# Rover-6_Power_Supply.net
KiCad netlist of a schematic drawn in EAGLE
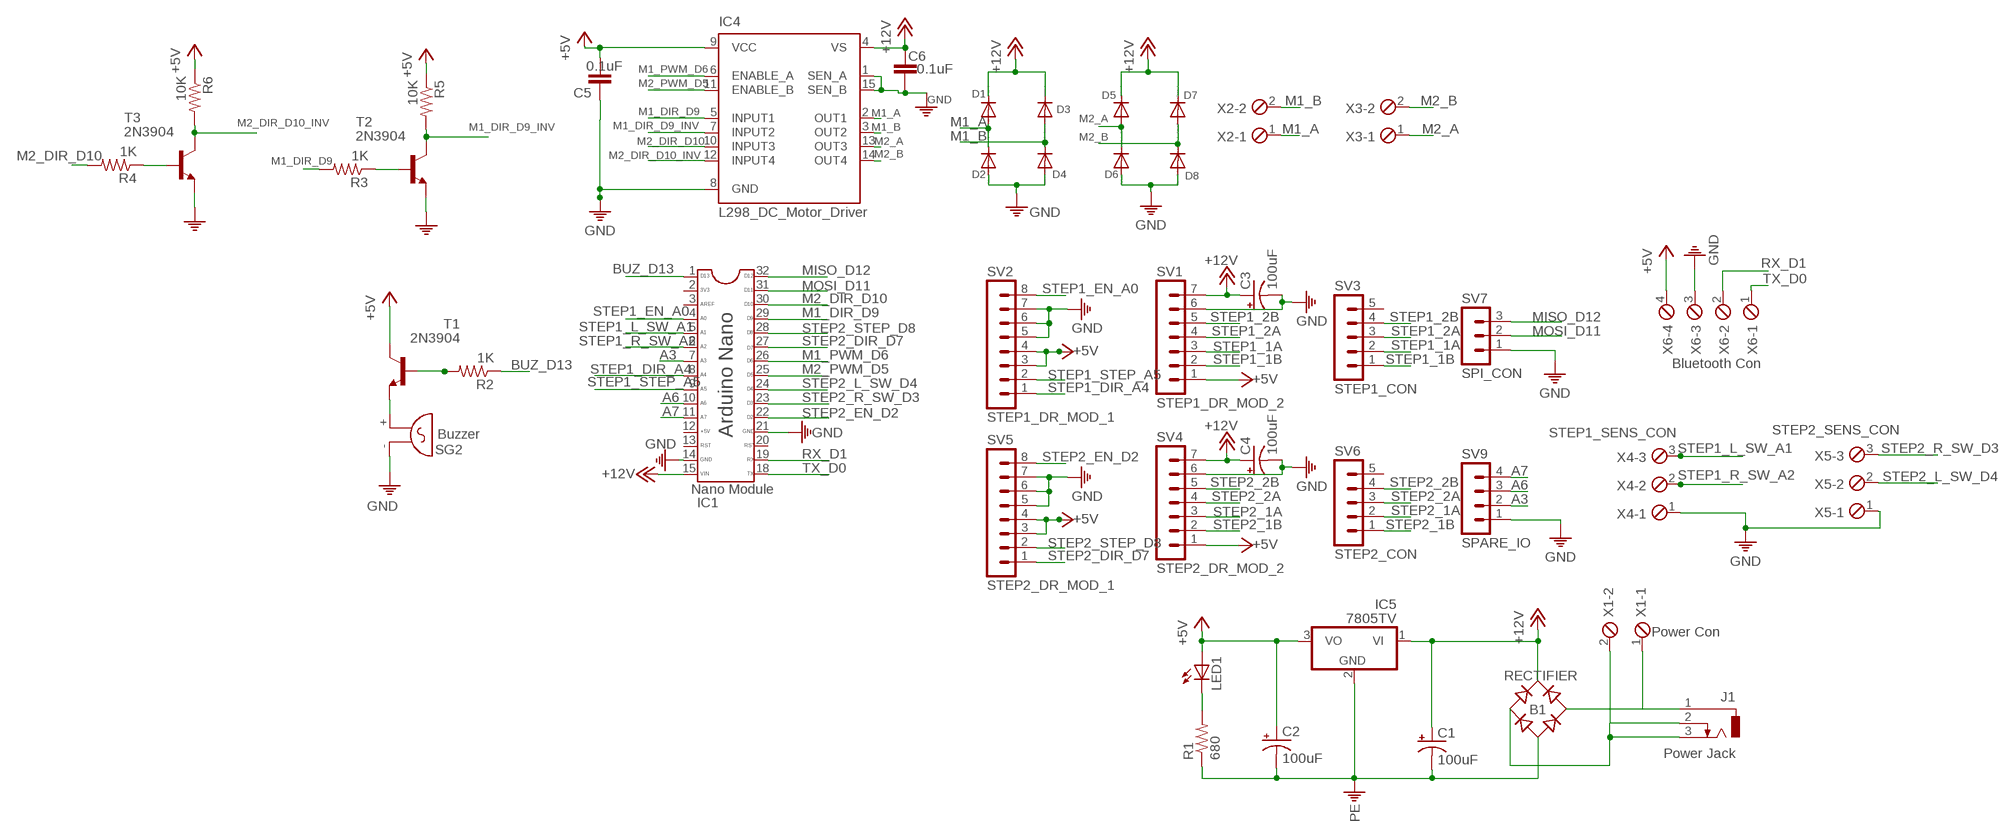
[diagram p0: schematic, sheet 1]

(export (version "E")
  (design (tool "Eeschema 10.0.6"))
  (components
    (comp (ref "B1")
      (value "RECTIFIER")
      (footprint "eagle-import:RB1A")
      (libsource (lib "eagle-import") (part "RB1A"))
    )
    (comp (ref "C1")
      (value "100uF")
      (footprint "eagle-import:E1,8-4")
      (libsource (lib "eagle-import") (part "CPOL-USE1.8-4"))
    )
    (comp (ref "C2")
      (value "100uF")
      (footprint "eagle-import:E1,8-4")
      (libsource (lib "eagle-import") (part "CPOL-USE1.8-4"))
    )
    (comp (ref "C3")
      (value "100uF")
      (footprint "eagle-import:E1,8-4")
      (libsource (lib "eagle-import") (part "CPOL-USE1.8-4"))
    )
    (comp (ref "C4")
      (value "100uF")
      (footprint "eagle-import:E1,8-4")
      (libsource (lib "eagle-import") (part "CPOL-USE1.8-4"))
    )
    (comp (ref "C5")
      (value "0.1uF")
      (footprint "eagle-import:C025-024X044")
      (libsource (lib "eagle-import") (part "C-EU025-024X044"))
    )
    (comp (ref "C6")
      (value "0.1uF")
      (footprint "eagle-import:C025-024X044")
      (libsource (lib "eagle-import") (part "C-EU025-024X044"))
    )
    (comp (ref "D1")
      (value "DIODE-D-2.5")
      (footprint "eagle-import:D-2.5")
      (libsource (lib "eagle-import") (part "DIODE-D-2.5"))
    )
    (comp (ref "D2")
      (value "DIODE-D-2.5")
      (footprint "eagle-import:D-2.5")
      (libsource (lib "eagle-import") (part "DIODE-D-2.5"))
    )
    (comp (ref "D3")
      (value "DIODE-D-2.5")
      (footprint "eagle-import:D-2.5")
      (libsource (lib "eagle-import") (part "DIODE-D-2.5"))
    )
    (comp (ref "D4")
      (value "DIODE-D-2.5")
      (footprint "eagle-import:D-2.5")
      (libsource (lib "eagle-import") (part "DIODE-D-2.5"))
    )
    (comp (ref "D5")
      (value "DIODE-D-2.5")
      (footprint "eagle-import:D-2.5")
      (libsource (lib "eagle-import") (part "DIODE-D-2.5"))
    )
    (comp (ref "D6")
      (value "DIODE-D-2.5")
      (footprint "eagle-import:D-2.5")
      (libsource (lib "eagle-import") (part "DIODE-D-2.5"))
    )
    (comp (ref "D7")
      (value "DIODE-D-2.5")
      (footprint "eagle-import:D-2.5")
      (libsource (lib "eagle-import") (part "DIODE-D-2.5"))
    )
    (comp (ref "D8")
      (value "DIODE-D-2.5")
      (footprint "eagle-import:D-2.5")
      (libsource (lib "eagle-import") (part "DIODE-D-2.5"))
    )
    (comp (ref "IC1")
      (value "Nano Module")
      (footprint "eagle-import:DIL32")
      (libsource (lib "eagle-import") (part "DIL32"))
    )
    (comp (ref "IC4")
      (value "L298_DC_Motor_Driver")
      (footprint "eagle-import:MULTIWATT-15")
      (fields (field (name "MPN") "L298N"))
      (libsource (lib "eagle-import") (part "L298"))
    )
    (comp (ref "IC5")
      (value "7805TV")
      (footprint "eagle-import:TO220V")
      (libsource (lib "eagle-import") (part "78TV05"))
    )
    (comp (ref "J1")
      (value "Power Jack")
      (footprint "eagle-import:ROVER-PW-JACL")
      (libsource (lib "eagle-import") (part "DCJ0303"))
    )
    (comp (ref "LED1")
      (value "LED3MM")
      (footprint "eagle-import:LED3MM")
      (libsource (lib "eagle-import") (part "LED3MM"))
    )
    (comp (ref "R1")
      (value "680")
      (footprint "eagle-import:0204_5")
      (libsource (lib "eagle-import") (part "R-US_0204/5"))
    )
    (comp (ref "R2")
      (value "1K")
      (footprint "eagle-import:0204_5")
      (libsource (lib "eagle-import") (part "R-US_0204/5"))
    )
    (comp (ref "R3")
      (value "1K")
      (footprint "eagle-import:0204_5")
      (libsource (lib "eagle-import") (part "R-US_0204/5"))
    )
    (comp (ref "R4")
      (value "1K")
      (footprint "eagle-import:0204_5")
      (libsource (lib "eagle-import") (part "R-US_0204/5"))
    )
    (comp (ref "R5")
      (value "10K")
      (footprint "eagle-import:0204_5")
      (libsource (lib "eagle-import") (part "R-US_0204/5"))
    )
    (comp (ref "R6")
      (value "10K")
      (footprint "eagle-import:0204_5")
      (libsource (lib "eagle-import") (part "R-US_0204/5"))
    )
    (comp (ref "SG2")
      (value "Buzzer")
      (footprint "eagle-import:F_QMX")
      (libsource (lib "eagle-import") (part "F/QMX"))
    )
    (comp (ref "SV1")
      (value "STEP1_DR_MOD_2")
      (footprint "eagle-import:MA07-1")
      (libsource (lib "eagle-import") (part "MA07-1"))
    )
    (comp (ref "SV2")
      (value "STEP1_DR_MOD_1")
      (footprint "eagle-import:MA08-1")
      (libsource (lib "eagle-import") (part "MA08-1"))
    )
    (comp (ref "SV3")
      (value "STEP1_CON")
      (footprint "eagle-import:MA05-1")
      (libsource (lib "eagle-import") (part "MA05-1"))
    )
    (comp (ref "SV4")
      (value "STEP2_DR_MOD_2")
      (footprint "eagle-import:MA07-1")
      (libsource (lib "eagle-import") (part "MA07-1"))
    )
    (comp (ref "SV5")
      (value "STEP2_DR_MOD_1")
      (footprint "eagle-import:MA08-1")
      (libsource (lib "eagle-import") (part "MA08-1"))
    )
    (comp (ref "SV6")
      (value "STEP2_CON")
      (footprint "eagle-import:MA05-1")
      (libsource (lib "eagle-import") (part "MA05-1"))
    )
    (comp (ref "SV7")
      (value "SPI_CON")
      (footprint "eagle-import:MA03-1")
      (libsource (lib "eagle-import") (part "MA03-1"))
    )
    (comp (ref "SV9")
      (value "SPARE_IO")
      (footprint "eagle-import:MA04-1")
      (libsource (lib "eagle-import") (part "MA04-1"))
    )
    (comp (ref "T1")
      (value "2N3904")
      (footprint "eagle-import:TO92")
      (libsource (lib "eagle-import") (part "2N3904"))
    )
    (comp (ref "T2")
      (value "2N3904")
      (footprint "eagle-import:TO92")
      (libsource (lib "eagle-import") (part "2N3904"))
    )
    (comp (ref "T3")
      (value "2N3904")
      (footprint "eagle-import:TO92")
      (libsource (lib "eagle-import") (part "2N3904"))
    )
    (comp (ref "X1")
      (value "Power Con")
      (footprint "eagle-import:2POL254")
      (libsource (lib "eagle-import") (part "MPT2"))
    )
    (comp (ref "X2")
      (value "MPT2")
      (footprint "eagle-import:2POL254")
      (libsource (lib "eagle-import") (part "MPT2"))
    )
    (comp (ref "X3")
      (value "MPT2")
      (footprint "eagle-import:2POL254")
      (libsource (lib "eagle-import") (part "MPT2"))
    )
    (comp (ref "X4")
      (value "STEP1_SENS_CON")
      (footprint "eagle-import:3POL254")
      (libsource (lib "eagle-import") (part "MPT3"))
    )
    (comp (ref "X5")
      (value "STEP2_SENS_CON")
      (footprint "eagle-import:3POL254")
      (libsource (lib "eagle-import") (part "MPT3"))
    )
    (comp (ref "X6")
      (value "Bluetooth Con")
      (footprint "eagle-import:4POL254")
      (libsource (lib "eagle-import") (part "MPT4"))
    )
  )
  (nets
    (net (code "1") (name "+5V") (class "Default")
      (node (ref "C2") (pin "+") (pinfunction "+_+") (pintype "passive"))
      (node (ref "C5") (pin "2") (pinfunction "2_2") (pintype "passive"))
      (node (ref "IC4") (pin "9") (pinfunction "VCC_9") (pintype "power_in"))
      (node (ref "IC5") (pin "3") (pinfunction "VO_3") (pintype "passive"))
      (node (ref "LED1") (pin "A") (pinfunction "A_A") (pintype "passive"))
      (node (ref "R5") (pin "1") (pinfunction "1_1") (pintype "passive"))
      (node (ref "R6") (pin "1") (pinfunction "1_1") (pintype "passive"))
      (node (ref "SV1") (pin "1") (pinfunction "1_1") (pintype "passive"))
      (node (ref "SV2") (pin "3") (pinfunction "3_3") (pintype "passive"))
      (node (ref "SV2") (pin "4") (pinfunction "4_4") (pintype "passive"))
      (node (ref "SV4") (pin "1") (pinfunction "1_1") (pintype "passive"))
      (node (ref "SV5") (pin "3") (pinfunction "3_3") (pintype "passive"))
      (node (ref "SV5") (pin "4") (pinfunction "4_4") (pintype "passive"))
      (node (ref "T1") (pin "1") (pinfunction "C_1") (pintype "passive"))
      (node (ref "X6") (pin "4") (pinfunction "1_4") (pintype "passive"))
    )
    (net (code "2") (name "+12V") (class "Default")
      (node (ref "B1") (pin "+") (pinfunction "+_+") (pintype "passive"))
      (node (ref "C1") (pin "+") (pinfunction "+_+") (pintype "passive"))
      (node (ref "C3") (pin "+") (pinfunction "+_+") (pintype "passive"))
      (node (ref "C4") (pin "+") (pinfunction "+_+") (pintype "passive"))
      (node (ref "C6") (pin "2") (pinfunction "2_2") (pintype "passive"))
      (node (ref "D1") (pin "C") (pinfunction "C_C") (pintype "passive"))
      (node (ref "D3") (pin "C") (pinfunction "C_C") (pintype "passive"))
      (node (ref "D5") (pin "C") (pinfunction "C_C") (pintype "passive"))
      (node (ref "D7") (pin "C") (pinfunction "C_C") (pintype "passive"))
      (node (ref "IC1") (pin "15") (pinfunction "VIN_15") (pintype "passive"))
      (node (ref "IC4") (pin "4") (pinfunction "VS_4") (pintype "power_in"))
      (node (ref "IC5") (pin "1") (pinfunction "VI_1") (pintype "input"))
      (node (ref "SV1") (pin "7") (pinfunction "7_7") (pintype "passive"))
      (node (ref "SV4") (pin "7") (pinfunction "7_7") (pintype "passive"))
    )
    (net (code "3") (name "/A3") (class "Default")
      (node (ref "IC1") (pin "7") (pinfunction "A3/D17_7") (pintype "passive"))
      (node (ref "SV9") (pin "2") (pinfunction "2_2") (pintype "passive"))
    )
    (net (code "4") (name "/A6") (class "Default")
      (node (ref "IC1") (pin "10") (pinfunction "A6_10") (pintype "passive"))
      (node (ref "SV9") (pin "3") (pinfunction "3_3") (pintype "passive"))
    )
    (net (code "5") (name "/A7") (class "Default")
      (node (ref "IC1") (pin "11") (pinfunction "A7_11") (pintype "passive"))
      (node (ref "SV9") (pin "4") (pinfunction "4_4") (pintype "passive"))
    )
    (net (code "6") (name "/BUZ_D13") (class "Default")
      (node (ref "IC1") (pin "1") (pinfunction "D13_1") (pintype "passive"))
      (node (ref "R2") (pin "1") (pinfunction "1_1") (pintype "passive"))
    )
    (net (code "7") (name "/M1_A") (class "Default")
      (node (ref "D1") (pin "A") (pinfunction "A_A") (pintype "passive"))
      (node (ref "D2") (pin "C") (pinfunction "C_C") (pintype "passive"))
      (node (ref "IC4") (pin "2") (pinfunction "OUT1_2") (pintype "output"))
      (node (ref "X2") (pin "1") (pinfunction "1_1") (pintype "passive"))
    )
    (net (code "8") (name "/M1_B") (class "Default")
      (node (ref "D3") (pin "A") (pinfunction "A_A") (pintype "passive"))
      (node (ref "D4") (pin "C") (pinfunction "C_C") (pintype "passive"))
      (node (ref "IC4") (pin "3") (pinfunction "OUT2_3") (pintype "output"))
      (node (ref "X2") (pin "2") (pinfunction "1_2") (pintype "passive"))
    )
    (net (code "9") (name "/M1_DIR_D9") (class "Default")
      (node (ref "IC1") (pin "29") (pinfunction "D9/PWM_29") (pintype "passive"))
      (node (ref "IC4") (pin "5") (pinfunction "INPUT1_5") (pintype "input"))
      (node (ref "R3") (pin "2") (pinfunction "2_2") (pintype "passive"))
    )
    (net (code "10") (name "/M1_DIR_D9_INV") (class "Default")
      (node (ref "IC4") (pin "7") (pinfunction "INPUT2_7") (pintype "input"))
      (node (ref "R5") (pin "2") (pinfunction "2_2") (pintype "passive"))
      (node (ref "T2") (pin "1") (pinfunction "C_1") (pintype "passive"))
    )
    (net (code "11") (name "/M1_PWM_D6") (class "Default")
      (node (ref "IC1") (pin "26") (pinfunction "D6/PWM_26") (pintype "passive"))
      (node (ref "IC4") (pin "6") (pinfunction "ENABLE_A_6") (pintype "input"))
    )
    (net (code "12") (name "/M2_A") (class "Default")
      (node (ref "D5") (pin "A") (pinfunction "A_A") (pintype "passive"))
      (node (ref "D6") (pin "C") (pinfunction "C_C") (pintype "passive"))
      (node (ref "IC4") (pin "13") (pinfunction "OUT3_13") (pintype "output"))
      (node (ref "X3") (pin "1") (pinfunction "1_1") (pintype "passive"))
    )
    (net (code "13") (name "/M2_B") (class "Default")
      (node (ref "D7") (pin "A") (pinfunction "A_A") (pintype "passive"))
      (node (ref "D8") (pin "C") (pinfunction "C_C") (pintype "passive"))
      (node (ref "IC4") (pin "14") (pinfunction "OUT4_14") (pintype "output"))
      (node (ref "X3") (pin "2") (pinfunction "1_2") (pintype "passive"))
    )
    (net (code "14") (name "/M2_DIR_D10") (class "Default")
      (node (ref "IC1") (pin "30") (pinfunction "D10/PWM_30") (pintype "passive"))
      (node (ref "IC4") (pin "10") (pinfunction "INPUT3_10") (pintype "input"))
      (node (ref "R4") (pin "2") (pinfunction "2_2") (pintype "passive"))
    )
    (net (code "15") (name "/M2_DIR_D10_INV") (class "Default")
      (node (ref "IC4") (pin "12") (pinfunction "INPUT4_12") (pintype "input"))
      (node (ref "R6") (pin "2") (pinfunction "2_2") (pintype "passive"))
      (node (ref "T3") (pin "1") (pinfunction "C_1") (pintype "passive"))
    )
    (net (code "16") (name "/M2_PWM_D5") (class "Default")
      (node (ref "IC1") (pin "25") (pinfunction "D5/PWM_25") (pintype "passive"))
      (node (ref "IC4") (pin "11") (pinfunction "ENABLE_B_11") (pintype "input"))
    )
    (net (code "17") (name "/MISO_D12") (class "Default")
      (node (ref "IC1") (pin "32") (pinfunction "D12/MISO_32") (pintype "passive"))
      (node (ref "SV7") (pin "3") (pinfunction "3_3") (pintype "passive"))
    )
    (net (code "18") (name "/MOSI_D11") (class "Default")
      (node (ref "IC1") (pin "31") (pinfunction "D11/MOSI_31") (pintype "passive"))
      (node (ref "SV7") (pin "2") (pinfunction "2_2") (pintype "passive"))
    )
    (net (code "19") (name "/RX_D1") (class "Default")
      (node (ref "IC1") (pin "19") (pinfunction "RX_19") (pintype "passive"))
      (node (ref "X6") (pin "2") (pinfunction "1_2") (pintype "passive"))
    )
    (net (code "20") (name "/STEP1_1A") (class "Default")
      (node (ref "SV1") (pin "3") (pinfunction "3_3") (pintype "passive"))
      (node (ref "SV3") (pin "2") (pinfunction "2_2") (pintype "passive"))
    )
    (net (code "21") (name "/STEP1_1B") (class "Default")
      (node (ref "SV1") (pin "2") (pinfunction "2_2") (pintype "passive"))
      (node (ref "SV3") (pin "1") (pinfunction "1_1") (pintype "passive"))
    )
    (net (code "22") (name "/STEP1_2A") (class "Default")
      (node (ref "SV1") (pin "4") (pinfunction "4_4") (pintype "passive"))
      (node (ref "SV3") (pin "3") (pinfunction "3_3") (pintype "passive"))
    )
    (net (code "23") (name "/STEP1_2B") (class "Default")
      (node (ref "SV1") (pin "5") (pinfunction "5_5") (pintype "passive"))
      (node (ref "SV3") (pin "4") (pinfunction "4_4") (pintype "passive"))
    )
    (net (code "24") (name "/STEP1_DIR_A4") (class "Default")
      (node (ref "IC1") (pin "8") (pinfunction "A4/D18/SDA_8") (pintype "passive"))
      (node (ref "SV2") (pin "1") (pinfunction "1_1") (pintype "passive"))
    )
    (net (code "25") (name "/STEP1_EN_A0") (class "Default")
      (node (ref "IC1") (pin "4") (pinfunction "A0/D14_4") (pintype "passive"))
      (node (ref "SV2") (pin "8") (pinfunction "8_8") (pintype "passive"))
    )
    (net (code "26") (name "/STEP1_L_SW_A1") (class "Default")
      (node (ref "IC1") (pin "5") (pinfunction "A1/D15_5") (pintype "passive"))
      (node (ref "X4") (pin "3") (pinfunction "1_3") (pintype "passive"))
    )
    (net (code "27") (name "/STEP1_R_SW_A2") (class "Default")
      (node (ref "IC1") (pin "6") (pinfunction "A2/D16_6") (pintype "passive"))
      (node (ref "X4") (pin "2") (pinfunction "1_2") (pintype "passive"))
    )
    (net (code "28") (name "/STEP1_STEP_A5") (class "Default")
      (node (ref "IC1") (pin "9") (pinfunction "A5/D19/SCL_9") (pintype "passive"))
      (node (ref "SV2") (pin "2") (pinfunction "2_2") (pintype "passive"))
    )
    (net (code "29") (name "/STEP2_1A") (class "Default")
      (node (ref "SV4") (pin "3") (pinfunction "3_3") (pintype "passive"))
      (node (ref "SV6") (pin "2") (pinfunction "2_2") (pintype "passive"))
    )
    (net (code "30") (name "/STEP2_1B") (class "Default")
      (node (ref "SV4") (pin "2") (pinfunction "2_2") (pintype "passive"))
      (node (ref "SV6") (pin "1") (pinfunction "1_1") (pintype "passive"))
    )
    (net (code "31") (name "/STEP2_2A") (class "Default")
      (node (ref "SV4") (pin "4") (pinfunction "4_4") (pintype "passive"))
      (node (ref "SV6") (pin "3") (pinfunction "3_3") (pintype "passive"))
    )
    (net (code "32") (name "/STEP2_2B") (class "Default")
      (node (ref "SV4") (pin "5") (pinfunction "5_5") (pintype "passive"))
      (node (ref "SV6") (pin "4") (pinfunction "4_4") (pintype "passive"))
    )
    (net (code "33") (name "/STEP2_DIR_D7") (class "Default")
      (node (ref "IC1") (pin "27") (pinfunction "D7_27") (pintype "passive"))
      (node (ref "SV5") (pin "1") (pinfunction "1_1") (pintype "passive"))
    )
    (net (code "34") (name "/STEP2_EN_D2") (class "Default")
      (node (ref "IC1") (pin "22") (pinfunction "D2_22") (pintype "passive"))
      (node (ref "SV5") (pin "8") (pinfunction "8_8") (pintype "passive"))
    )
    (net (code "35") (name "/STEP2_L_SW_D4") (class "Default")
      (node (ref "IC1") (pin "24") (pinfunction "D4_24") (pintype "passive"))
      (node (ref "X5") (pin "2") (pinfunction "1_2") (pintype "passive"))
    )
    (net (code "36") (name "/STEP2_R_SW_D3") (class "Default")
      (node (ref "IC1") (pin "23") (pinfunction "D3_23") (pintype "passive"))
      (node (ref "X5") (pin "3") (pinfunction "1_3") (pintype "passive"))
    )
    (net (code "37") (name "/STEP2_STEP_D8") (class "Default")
      (node (ref "IC1") (pin "28") (pinfunction "D8_28") (pintype "passive"))
      (node (ref "SV5") (pin "2") (pinfunction "2_2") (pintype "passive"))
    )
    (net (code "38") (name "/TX_D0") (class "Default")
      (node (ref "IC1") (pin "18") (pinfunction "TX_18") (pintype "passive"))
      (node (ref "X6") (pin "1") (pinfunction "1_1") (pintype "passive"))
    )
    (net (code "39") (name "GND") (class "Default")
      (node (ref "B1") (pin "-") (pinfunction "-_-") (pintype "passive"))
      (node (ref "C1") (pin "-") (pinfunction "-_-") (pintype "passive"))
      (node (ref "C2") (pin "-") (pinfunction "-_-") (pintype "passive"))
      (node (ref "C3") (pin "-") (pinfunction "-_-") (pintype "passive"))
      (node (ref "C4") (pin "-") (pinfunction "-_-") (pintype "passive"))
      (node (ref "C5") (pin "1") (pinfunction "1_1") (pintype "passive"))
      (node (ref "C6") (pin "1") (pinfunction "1_1") (pintype "passive"))
      (node (ref "D2") (pin "A") (pinfunction "A_A") (pintype "passive"))
      (node (ref "D4") (pin "A") (pinfunction "A_A") (pintype "passive"))
      (node (ref "D6") (pin "A") (pinfunction "A_A") (pintype "passive"))
      (node (ref "D8") (pin "A") (pinfunction "A_A") (pintype "passive"))
      (node (ref "IC1") (pin "14") (pinfunction "GND1_14") (pintype "passive"))
      (node (ref "IC1") (pin "21") (pinfunction "GND2_21") (pintype "passive"))
      (node (ref "IC4") (pin "1") (pinfunction "SEN_A_1") (pintype "input"))
      (node (ref "IC4") (pin "15") (pinfunction "SEN_B_15") (pintype "input"))
      (node (ref "IC4") (pin "8") (pinfunction "GND_8") (pintype "power_in"))
      (node (ref "IC5") (pin "2") (pinfunction "GND_2") (pintype "passive"))
      (node (ref "R1") (pin "1") (pinfunction "1_1") (pintype "passive"))
      (node (ref "SG2") (pin "-") (pinfunction "1_-") (pintype "passive"))
      (node (ref "SV1") (pin "6") (pinfunction "6_6") (pintype "passive"))
      (node (ref "SV2") (pin "5") (pinfunction "5_5") (pintype "passive"))
      (node (ref "SV2") (pin "6") (pinfunction "6_6") (pintype "passive"))
      (node (ref "SV2") (pin "7") (pinfunction "7_7") (pintype "passive"))
      (node (ref "SV4") (pin "6") (pinfunction "6_6") (pintype "passive"))
      (node (ref "SV5") (pin "5") (pinfunction "5_5") (pintype "passive"))
      (node (ref "SV5") (pin "6") (pinfunction "6_6") (pintype "passive"))
      (node (ref "SV5") (pin "7") (pinfunction "7_7") (pintype "passive"))
      (node (ref "SV7") (pin "1") (pinfunction "1_1") (pintype "passive"))
      (node (ref "SV9") (pin "1") (pinfunction "1_1") (pintype "passive"))
      (node (ref "T2") (pin "3") (pinfunction "E_3") (pintype "passive"))
      (node (ref "T3") (pin "3") (pinfunction "E_3") (pintype "passive"))
      (node (ref "X4") (pin "1") (pinfunction "1_1") (pintype "passive"))
      (node (ref "X5") (pin "1") (pinfunction "1_1") (pintype "passive"))
      (node (ref "X6") (pin "3") (pinfunction "1_3") (pintype "passive"))
    )
    (net (code "40") (name "Net-(B1-PadAC1)") (class "Default")
      (node (ref "B1") (pin "AC1") (pinfunction "AC1_AC1") (pintype "passive"))
      (node (ref "J1") (pin "1") (pinfunction "1_1") (pintype "passive"))
      (node (ref "X1") (pin "1") (pinfunction "1_1") (pintype "passive"))
    )
    (net (code "41") (name "Net-(LED1-C)") (class "Default")
      (node (ref "LED1") (pin "K") (pinfunction "C_K") (pintype "passive"))
      (node (ref "R1") (pin "2") (pinfunction "2_2") (pintype "passive"))
    )
    (net (code "42") (name "Net-(SG2-2)") (class "Default")
      (node (ref "SG2") (pin "+") (pinfunction "2_+") (pintype "passive"))
      (node (ref "T1") (pin "3") (pinfunction "E_3") (pintype "passive"))
    )
    (net (code "43") (name "Net-(T1-B)") (class "Default")
      (node (ref "R2") (pin "2") (pinfunction "2_2") (pintype "passive"))
      (node (ref "T1") (pin "2") (pinfunction "B_2") (pintype "passive"))
    )
    (net (code "44") (name "Net-(T2-B)") (class "Default")
      (node (ref "R3") (pin "1") (pinfunction "1_1") (pintype "passive"))
      (node (ref "T2") (pin "2") (pinfunction "B_2") (pintype "passive"))
    )
    (net (code "45") (name "Net-(T3-B)") (class "Default")
      (node (ref "R4") (pin "1") (pinfunction "1_1") (pintype "passive"))
      (node (ref "T3") (pin "2") (pinfunction "B_2") (pintype "passive"))
    )
    (net (code "46") (name "Net-(X1B-1)") (class "Default")
      (node (ref "B1") (pin "AC2") (pinfunction "AC2_AC2") (pintype "passive"))
      (node (ref "J1") (pin "2") (pinfunction "2_2") (pintype "passive"))
      (node (ref "J1") (pin "3") (pinfunction "3_3") (pintype "passive"))
      (node (ref "X1") (pin "2") (pinfunction "1_2") (pintype "passive"))
    )
    (net (code "47") (name "unconnected-(IC1-3V3-Pad2)") (class "Default")
      (node (ref "IC1") (pin "2") (pinfunction "3V3_2") (pintype "passive"))
    )
    (net (code "48") (name "unconnected-(IC1-5V-Pad12)") (class "Default")
      (node (ref "IC1") (pin "12") (pinfunction "5V_12") (pintype "passive"))
    )
    (net (code "49") (name "unconnected-(IC1-AREF-Pad3)") (class "Default")
      (node (ref "IC1") (pin "3") (pinfunction "AREF_3") (pintype "passive"))
    )
    (net (code "50") (name "unconnected-(IC1-RST1-Pad13)") (class "Default")
      (node (ref "IC1") (pin "13") (pinfunction "RST1_13") (pintype "passive"))
    )
    (net (code "51") (name "unconnected-(IC1-RST2-Pad20)") (class "Default")
      (node (ref "IC1") (pin "20") (pinfunction "RST2_20") (pintype "passive"))
    )
    (net (code "52") (name "unconnected-(SV3-Pad5)") (class "Default")
      (node (ref "SV3") (pin "5") (pinfunction "5_5") (pintype "passive"))
    )
    (net (code "53") (name "unconnected-(SV6-Pad5)") (class "Default")
      (node (ref "SV6") (pin "5") (pinfunction "5_5") (pintype "passive"))
    )
  )
)
